# Main.net
KiCad netlist of a schematic drawn in Altium Designer
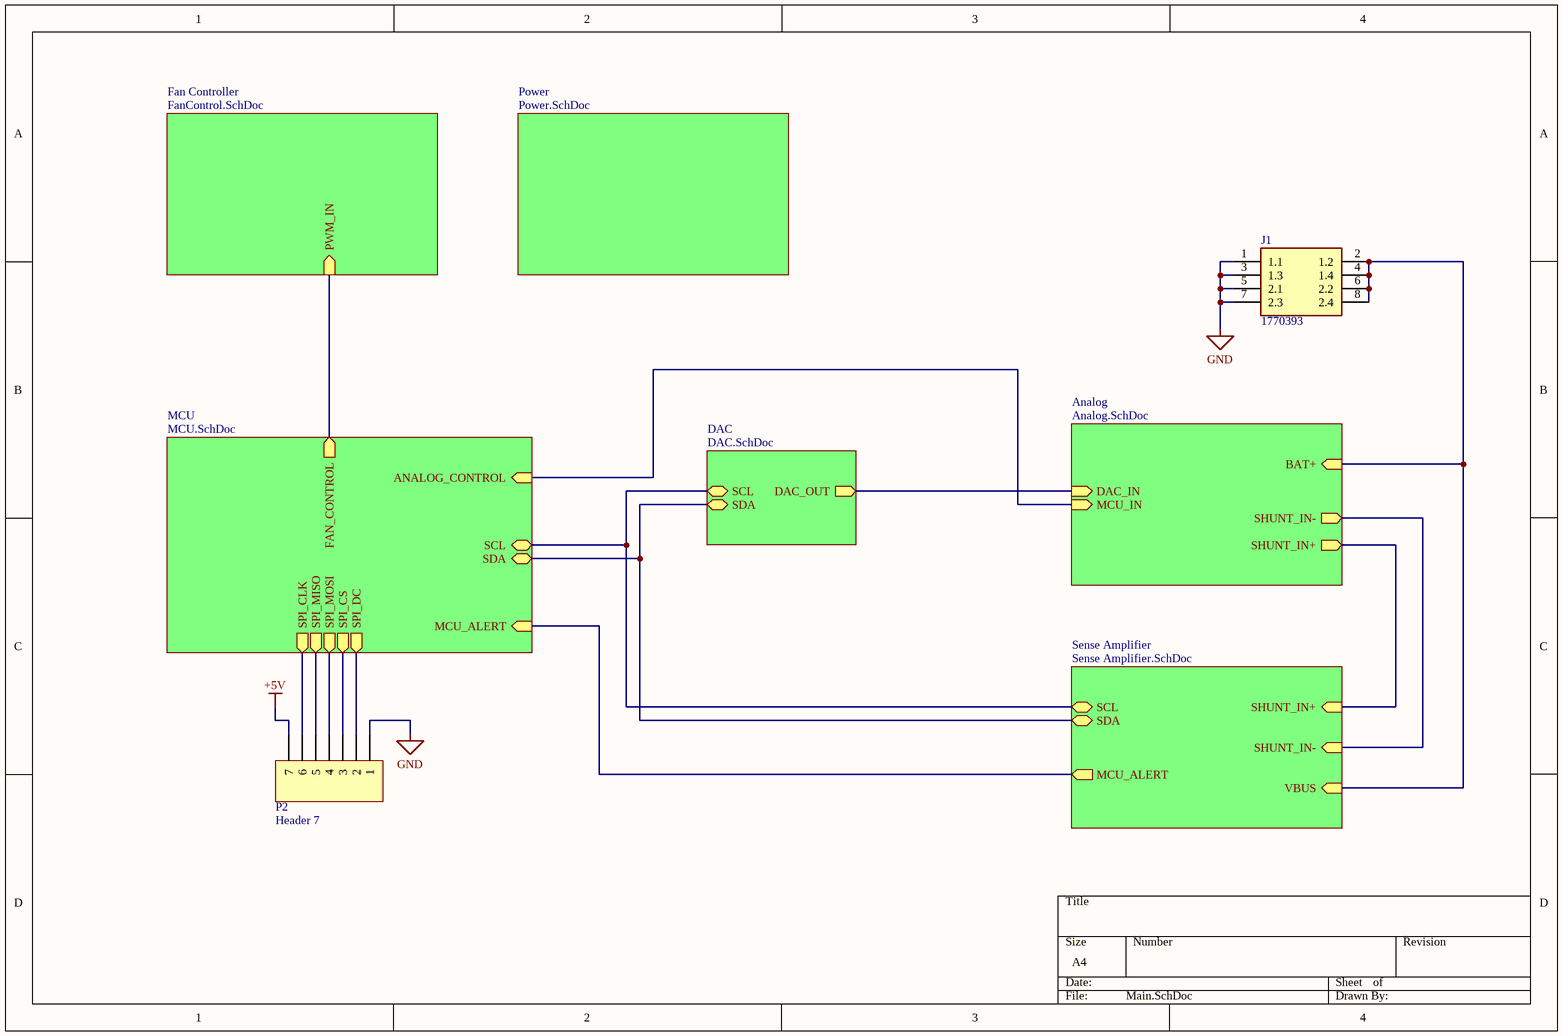
[diagram p0: Main.SchDoc]

(export (version "E")
  (design (tool "Eeschema 10.0.6"))
  (components
    (comp (ref "J1")
      (value "1770393")
      (footprint "SamacSys:1770393")
      (description "Connector")
      (fields (field (name "MOUSER PART NUMBER") "651-1770393"))
      (libsource (lib "SamacSys") (part "1770393"))
    )
    (comp (ref "P2")
      (value "Header 7")
      (footprint "HDR1X7")
      (description "Header, 7-Pin")
      (fields (field (name "PUBLISHER") "Altium Limited"))
      (libsource (lib "Miscellaneous Connectors") (part "Header 7"))
    )
  )
  (nets
    (net (code "1") (name "+5V") (class "Default")
      (node (ref "P2") (pin "7") (pinfunction "7_7") (pintype "passive"))
    )
    (net (code "3") (name "/BAT+") (class "Default")
      (node (ref "J1") (pin "2") (pinfunction "1.2_2") (pintype "passive"))
      (node (ref "J1") (pin "4") (pinfunction "1.4_4") (pintype "passive"))
      (node (ref "J1") (pin "6") (pinfunction "2.2_6") (pintype "passive"))
      (node (ref "J1") (pin "8") (pinfunction "2.4_8") (pintype "passive"))
    )
    (net (code "11") (name "/SPI_CLK") (class "Default")
      (node (ref "P2") (pin "6") (pinfunction "6_6") (pintype "passive"))
    )
    (net (code "12") (name "/SPI_CS") (class "Default")
      (node (ref "P2") (pin "3") (pinfunction "3_3") (pintype "passive"))
    )
    (net (code "13") (name "/SPI_DC") (class "Default")
      (node (ref "P2") (pin "2") (pinfunction "2_2") (pintype "passive"))
    )
    (net (code "14") (name "/SPI_MISO") (class "Default")
      (node (ref "P2") (pin "5") (pinfunction "5_5") (pintype "passive"))
    )
    (net (code "15") (name "/SPI_MOSI") (class "Default")
      (node (ref "P2") (pin "4") (pinfunction "4_4") (pintype "passive"))
    )
    (net (code "16") (name "GND") (class "Default")
      (node (ref "J1") (pin "1") (pinfunction "1.1_1") (pintype "passive"))
      (node (ref "J1") (pin "3") (pinfunction "1.3_3") (pintype "passive"))
      (node (ref "J1") (pin "5") (pinfunction "2.1_5") (pintype "passive"))
      (node (ref "J1") (pin "7") (pinfunction "2.3_7") (pintype "passive"))
      (node (ref "P2") (pin "1") (pinfunction "1_1") (pintype "passive"))
    )
  )
)
